# VIC-20_Diag_Keyboard.net
KiCad netlist of a schematic drawn in EAGLE
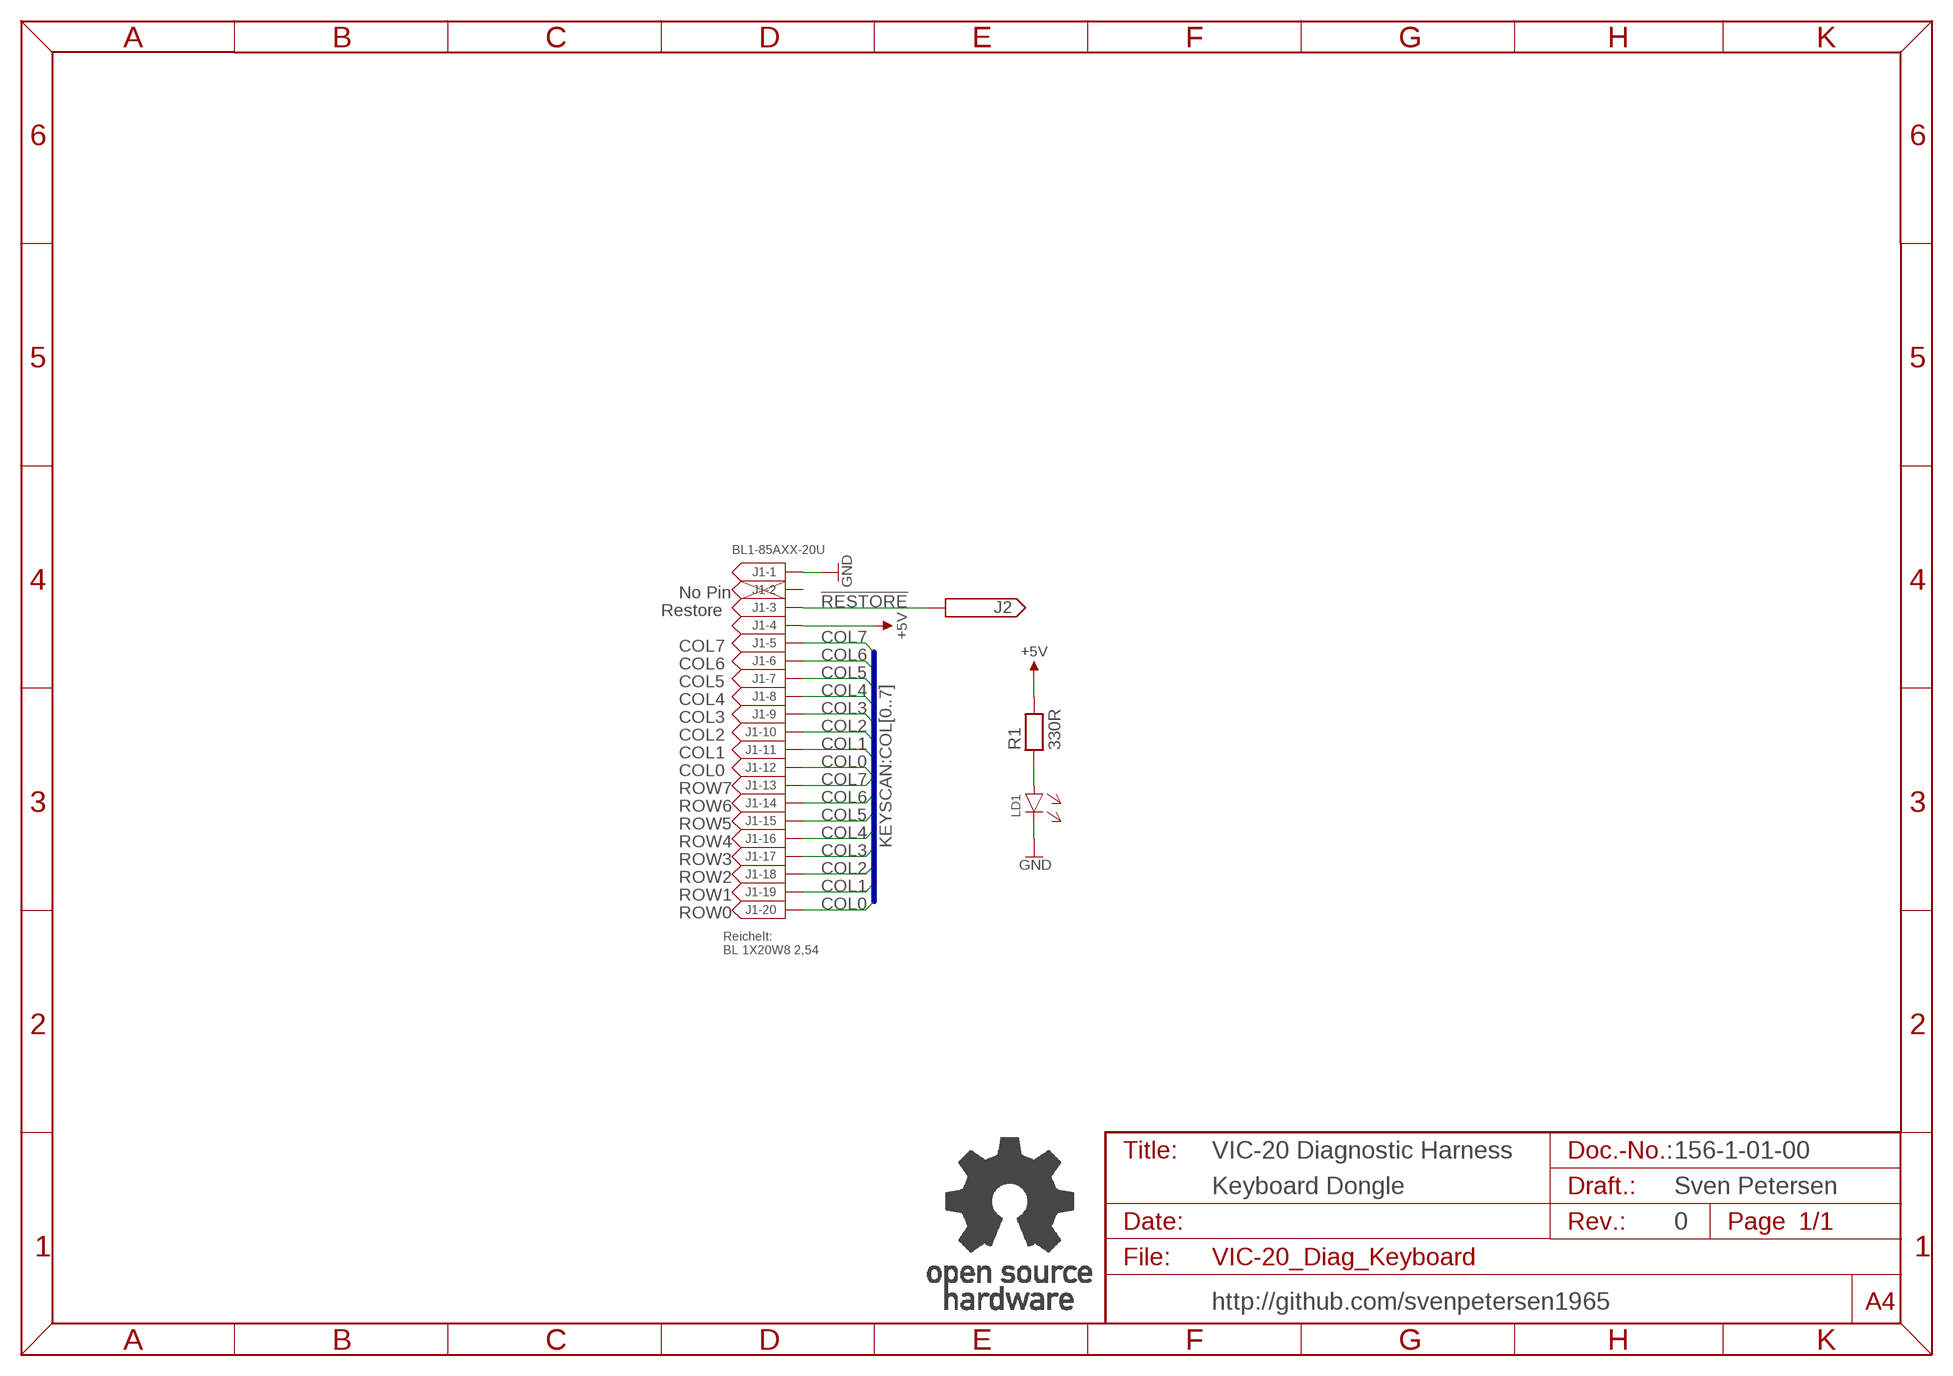
[diagram p0: schematic, sheet 1]

(export (version "E")
  (design (tool "Eeschema 10.0.6"))
  (components
    (comp (ref "J1")
      (value "BL1-85AXX-20U")
      (footprint "eagle-import:BL1-85AXX-20U")
      (libsource (lib "eagle-import") (part "BL1-85AXX-20U"))
    )
    (comp (ref "J2")
      (value "PINHD-1X1")
      (footprint "eagle-import:1X01")
      (libsource (lib "eagle-import") (part "PINHD-1X1"))
    )
    (comp (ref "LD1")
      (value "3MM")
      (footprint "eagle-import:3MM")
      (libsource (lib "eagle-import") (part "3MM"))
    )
    (comp (ref "R1")
      (value "330R")
      (footprint "eagle-import:R-10")
      (libsource (lib "eagle-import") (part "RES04"))
    )
    (comp (ref "U$9")
      (value "OPEN_SOURCE_HW")
      (footprint "eagle-import:OPENHW")
      (libsource (lib "eagle-import") (part "OPEN_SOURCE_HW"))
    )
  )
  (nets
    (net (code "9") (name "+5V") (class "Default")
      (node (ref "J1") (pin "4") (pinfunction "1_4") (pintype "bidirectional"))
      (node (ref "R1") (pin "2") (pinfunction "2_2") (pintype "passive"))
    )
    (net (code "10") (name "/COL0") (class "Default")
      (node (ref "J1") (pin "12") (pinfunction "1_12") (pintype "bidirectional"))
      (node (ref "J1") (pin "20") (pinfunction "1_20") (pintype "bidirectional"))
    )
    (net (code "11") (name "/COL1") (class "Default")
      (node (ref "J1") (pin "11") (pinfunction "1_11") (pintype "bidirectional"))
      (node (ref "J1") (pin "19") (pinfunction "1_19") (pintype "bidirectional"))
    )
    (net (code "12") (name "/COL2") (class "Default")
      (node (ref "J1") (pin "10") (pinfunction "1_10") (pintype "bidirectional"))
      (node (ref "J1") (pin "18") (pinfunction "1_18") (pintype "bidirectional"))
    )
    (net (code "13") (name "/COL3") (class "Default")
      (node (ref "J1") (pin "17") (pinfunction "1_17") (pintype "bidirectional"))
      (node (ref "J1") (pin "9") (pinfunction "1_9") (pintype "bidirectional"))
    )
    (net (code "14") (name "/COL4") (class "Default")
      (node (ref "J1") (pin "16") (pinfunction "1_16") (pintype "bidirectional"))
      (node (ref "J1") (pin "8") (pinfunction "1_8") (pintype "bidirectional"))
    )
    (net (code "15") (name "/COL5") (class "Default")
      (node (ref "J1") (pin "15") (pinfunction "1_15") (pintype "bidirectional"))
      (node (ref "J1") (pin "7") (pinfunction "1_7") (pintype "bidirectional"))
    )
    (net (code "16") (name "/COL6") (class "Default")
      (node (ref "J1") (pin "14") (pinfunction "1_14") (pintype "bidirectional"))
      (node (ref "J1") (pin "6") (pinfunction "1_6") (pintype "bidirectional"))
    )
    (net (code "17") (name "/COL7") (class "Default")
      (node (ref "J1") (pin "13") (pinfunction "1_13") (pintype "bidirectional"))
      (node (ref "J1") (pin "5") (pinfunction "1_5") (pintype "bidirectional"))
    )
    (net (code "19") (name "/~{RESTORE}") (class "Default")
      (node (ref "J1") (pin "3") (pinfunction "1_3") (pintype "bidirectional"))
      (node (ref "J2") (pin "1") (pinfunction "1_1") (pintype "passive"))
    )
    (net (code "20") (name "GND") (class "Default")
      (node (ref "J1") (pin "1") (pinfunction "1_1") (pintype "bidirectional"))
      (node (ref "LD1") (pin "C") (pinfunction "K_C") (pintype "bidirectional"))
    )
    (net (code "21") (name "Net-(LD1-PadA)") (class "Default")
      (node (ref "LD1") (pin "A") (pinfunction "A_A") (pintype "bidirectional"))
      (node (ref "R1") (pin "1") (pinfunction "1_1") (pintype "passive"))
    )
    (net (code "22") (name "unconnected-(J1L-1-Pad2)") (class "Default")
      (node (ref "J1") (pin "2") (pinfunction "1_2") (pintype "bidirectional"))
    )
  )
)
